# sch_Connet_IMU.net
KiCad netlist of a schematic drawn in Altium Designer
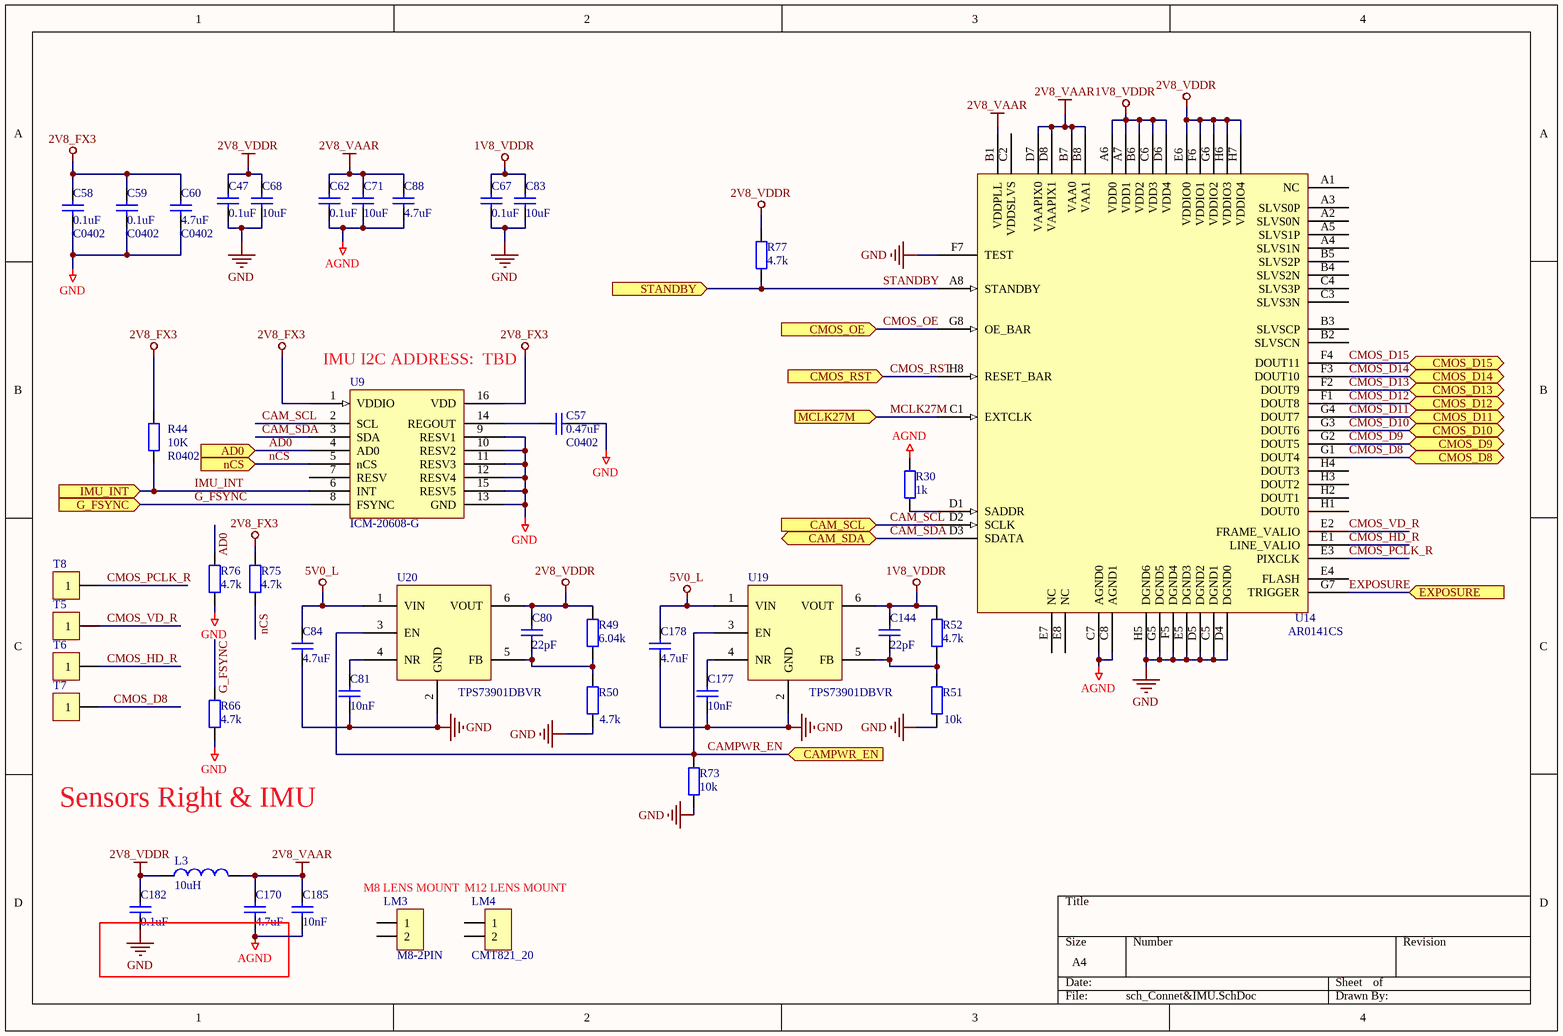
[diagram p0: sch_Connet&IMU.SchDoc]

(export (version "E")
  (design (tool "Eeschema 10.0.6"))
  (components
    (comp (ref "C47")
      (value "0.1uF")
      (footprint "0402C")
      (description "Capacitor")
      (fields (field (name "PUBLISHER") "Altium Limited"))
      (libsource (lib "Miscellaneous Devices") (part "Cap"))
    )
    (comp (ref "C57")
      (value "0.47uF")
      (footprint "0402C")
      (description "Capacitor")
      (fields (field (name "ALTIUM_VALUE") "C0402") (field (name "PUBLISHER") "Altium Limited"))
      (libsource (lib "Miscellaneous Devices") (part "Cap"))
    )
    (comp (ref "C58")
      (value "0.1uF")
      (footprint "0402C")
      (description "Capacitor")
      (fields (field (name "ALTIUM_VALUE") "C0402") (field (name "PUBLISHER") "Altium Limited"))
      (libsource (lib "Miscellaneous Devices") (part "Cap"))
    )
    (comp (ref "C59")
      (value "0.1uF")
      (footprint "0402C")
      (description "Capacitor")
      (fields (field (name "ALTIUM_VALUE") "C0402") (field (name "PUBLISHER") "Altium Limited"))
      (libsource (lib "Miscellaneous Devices") (part "Cap"))
    )
    (comp (ref "C60")
      (value "4.7uF")
      (footprint "0402C")
      (description "Capacitor")
      (fields (field (name "ALTIUM_VALUE") "C0402") (field (name "PUBLISHER") "Altium Limited"))
      (libsource (lib "Miscellaneous Devices") (part "Cap"))
    )
    (comp (ref "C62")
      (value "0.1uF")
      (footprint "0402C")
      (description "Capacitor")
      (fields (field (name "PUBLISHER") "Altium Limited"))
      (libsource (lib "Miscellaneous Devices") (part "Cap"))
    )
    (comp (ref "C67")
      (value "0.1uF")
      (footprint "0402C")
      (description "Capacitor")
      (fields (field (name "PUBLISHER") "Altium Limited"))
      (libsource (lib "Miscellaneous Devices") (part "Cap"))
    )
    (comp (ref "C68")
      (value "10uF")
      (footprint "0805C")
      (description "Capacitor")
      (fields (field (name "PUBLISHER") "Altium Limited"))
      (libsource (lib "Miscellaneous Devices") (part "Cap"))
    )
    (comp (ref "C71")
      (value "10uF")
      (footprint "0805C")
      (description "Capacitor")
      (fields (field (name "PUBLISHER") "Altium Limited"))
      (libsource (lib "Miscellaneous Devices") (part "Cap"))
    )
    (comp (ref "C80")
      (value "22pF")
      (footprint "0805C")
      (description "Capacitor")
      (fields (field (name "PUBLISHER") "Altium Limited"))
      (libsource (lib "Miscellaneous Devices") (part "Cap"))
    )
    (comp (ref "C81")
      (value "10nF")
      (footprint "0402C_L")
      (description "Capacitor")
      (fields (field (name "PUBLISHER") "Altium Limited"))
      (libsource (lib "Miscellaneous Devices") (part "Cap"))
    )
    (comp (ref "C83")
      (value "10uF")
      (footprint "0805C")
      (description "Capacitor")
      (fields (field (name "PUBLISHER") "Altium Limited"))
      (libsource (lib "Miscellaneous Devices") (part "Cap"))
    )
    (comp (ref "C84")
      (value "4.7uF")
      (footprint "0402C_L")
      (description "Capacitor")
      (fields (field (name "PUBLISHER") "Altium Limited"))
      (libsource (lib "Miscellaneous Devices") (part "Cap"))
    )
    (comp (ref "C88")
      (value "4.7uF")
      (footprint "0805C")
      (description "Capacitor")
      (fields (field (name "PUBLISHER") "Altium Limited"))
      (libsource (lib "Miscellaneous Devices") (part "Cap"))
    )
    (comp (ref "C144")
      (value "22pF")
      (footprint "0402C")
      (description "Capacitor")
      (fields (field (name "PUBLISHER") "Altium Limited"))
      (libsource (lib "Miscellaneous Devices") (part "Cap"))
    )
    (comp (ref "C170")
      (value "4.7uF")
      (footprint "0402C")
      (description "Capacitor")
      (fields (field (name "PUBLISHER") "Altium Limited"))
      (libsource (lib "Miscellaneous Devices") (part "Cap"))
    )
    (comp (ref "C177")
      (value "10nF")
      (footprint "0402C_L")
      (description "Capacitor")
      (fields (field (name "PUBLISHER") "Altium Limited"))
      (libsource (lib "Miscellaneous Devices") (part "Cap"))
    )
    (comp (ref "C178")
      (value "4.7uF")
      (footprint "0402C_L")
      (description "Capacitor")
      (fields (field (name "PUBLISHER") "Altium Limited"))
      (libsource (lib "Miscellaneous Devices") (part "Cap"))
    )
    (comp (ref "C182")
      (value "0.1uF")
      (footprint "0402C_L")
      (description "Capacitor")
      (fields (field (name "PUBLISHER") "Altium Limited"))
      (libsource (lib "Miscellaneous Devices") (part "Cap"))
    )
    (comp (ref "C185")
      (value "10nF")
      (footprint "0402C_L")
      (description "Capacitor")
      (fields (field (name "PUBLISHER") "Altium Limited"))
      (libsource (lib "Miscellaneous Devices") (part "Cap"))
    )
    (comp (ref "L3")
      (value "10uH")
      (footprint "0805R")
      (description "Inductor")
      (libsource (lib "SWUST_ROBOT") (part "Inductor"))
    )
    (comp (ref "LM3")
      (value "M8-2PIN")
      (footprint "PAD_M3_D350_450")
      (description "Connector")
      (libsource (lib "SuperSchLib") (part "CON2"))
    )
    (comp (ref "LM4")
      (value "CMT821_20")
      (footprint "PAD_M3_D350_450")
      (description "Connector")
      (libsource (lib "SuperSchLib") (part "CON2"))
    )
    (comp (ref "R30")
      (value "1k")
      (footprint "0402R")
      (description "Resistor")
      (fields (field (name "PUBLISHER") "Altium Limited"))
      (libsource (lib "") (part "Res2_1"))
    )
    (comp (ref "R44")
      (value "10K")
      (footprint "0402R")
      (description "Resistor")
      (fields (field (name "ALTIUM_VALUE") "R0402") (field (name "PUBLISHER") "Altium Limited"))
      (libsource (lib "Miscellaneous Devices") (part "Res2"))
    )
    (comp (ref "R49")
      (value "6.04k")
      (footprint "0402R")
      (description "Resistor")
      (fields (field (name "Comment") "6.04K") (field (name "PUBLISHER") "Altium Limited"))
      (libsource (lib "") (part "Resistor_1"))
    )
    (comp (ref "R50")
      (value "4.7k")
      (footprint "0402R")
      (description "Resistor")
      (fields (field (name "Comment") "4.7K") (field (name "PUBLISHER") "Altium Limited"))
      (libsource (lib "SZG") (part "Resistor"))
    )
    (comp (ref "R51")
      (value "10k")
      (footprint "0402R")
      (description "Resistor")
      (fields (field (name "Comment") "10K") (field (name "PUBLISHER") "Altium Limited"))
      (libsource (lib "SZG") (part "Resistor"))
    )
    (comp (ref "R52")
      (value "4.7k")
      (footprint "0402R")
      (description "Resistor")
      (fields (field (name "Comment") "4.7K") (field (name "PUBLISHER") "Altium Limited"))
      (libsource (lib "") (part "Resistor_1"))
    )
    (comp (ref "R66")
      (value "4.7k")
      (footprint "0402R")
      (description "Resistor")
      (fields (field (name "Comment") "4.7K") (field (name "PUBLISHER") "Altium Limited"))
      (libsource (lib "") (part "Resistor_1"))
    )
    (comp (ref "R73")
      (value "10k")
      (footprint "0402R_L")
      (description "Resistor")
      (fields (field (name "Comment") "10K") (field (name "PUBLISHER") "Altium Limited"))
      (libsource (lib "") (part "Resistor_2"))
    )
    (comp (ref "R75")
      (value "4.7k")
      (footprint "0402R")
      (description "Resistor")
      (fields (field (name "Comment") "4.7K") (field (name "PUBLISHER") "Altium Limited"))
      (libsource (lib "") (part "Resistor_1"))
    )
    (comp (ref "R76")
      (value "4.7k")
      (footprint "0402R")
      (description "Resistor")
      (fields (field (name "Comment") "4.7K") (field (name "PUBLISHER") "Altium Limited"))
      (libsource (lib "") (part "Resistor_1"))
    )
    (comp (ref "R77")
      (value "4.7k")
      (footprint "0402R")
      (description "Resistor")
      (fields (field (name "Comment") "4.7K") (field (name "PUBLISHER") "Altium Limited"))
      (libsource (lib "") (part "Resistor_1"))
    )
    (comp (ref "T5")
      (value "CON1")
      (footprint "PAD_TP_D1.2")
      (description "Connector")
      (libsource (lib "SuperSchLib") (part "CON1"))
    )
    (comp (ref "T6")
      (value "CON1")
      (footprint "PAD_TP_D1.2")
      (description "Connector")
      (libsource (lib "SuperSchLib") (part "CON1"))
    )
    (comp (ref "T7")
      (value "CON1")
      (footprint "PAD_TP_D1.2")
      (description "Connector")
      (libsource (lib "SuperSchLib") (part "CON1"))
    )
    (comp (ref "T8")
      (value "CON1")
      (footprint "PAD_TP_D1.2")
      (description "Connector")
      (libsource (lib "SuperSchLib") (part "CON1"))
    )
    (comp (ref "U9")
      (value "ICM-20608-G")
      (footprint "LGA16_P50L30W30H08")
      (libsource (lib "SZG") (part "ICM-20608-G"))
    )
    (comp (ref "U14") (value "AR0141CS") (libsource (lib "TXW") (part "AR0141CS")))
    (comp (ref "U19") (value "TPS73901DBVR") (libsource (lib "SZG") (part "TPS73901DBVR")))
    (comp (ref "U20") (value "TPS73901DBVR") (libsource (lib "SZG") (part "TPS73901DBVR")))
  )
  (nets
    (net (code "1") (name "/AD0") (class "Default")
      (node (ref "R76") (pin "2") (pinfunction "2_2") (pintype "passive"))
      (node (ref "U9") (pin "4") (pinfunction "AD0_4") (pintype "passive"))
    )
    (net (code "2") (name "/CAMPWR_EN") (class "Default")
      (node (ref "R73") (pin "1") (pinfunction "1_1") (pintype "passive"))
      (node (ref "U19") (pin "3") (pinfunction "EN_3") (pintype "passive"))
      (node (ref "U20") (pin "3") (pinfunction "EN_3") (pintype "passive"))
    )
    (net (code "3") (name "/CAM_SCL") (class "Default")
      (node (ref "U14") (pin "D2") (pinfunction "SCLK_D2") (pintype "input"))
      (node (ref "U9") (pin "2") (pinfunction "SCL_2") (pintype "passive"))
    )
    (net (code "4") (name "/CAM_SDA") (class "Default")
      (node (ref "U14") (pin "D3") (pinfunction "SDATA_D3") (pintype "passive"))
      (node (ref "U9") (pin "3") (pinfunction "SDA_3") (pintype "passive"))
    )
    (net (code "5") (name "/CMOS_D8") (class "Default")
      (node (ref "T7") (pin "1") (pinfunction "1_1") (pintype "passive"))
      (node (ref "U14") (pin "G1") (pinfunction "DOUT4_G1") (pintype "passive"))
    )
    (net (code "6") (name "/CMOS_D9") (class "Default")
      (node (ref "U14") (pin "G2") (pinfunction "DOUT5_G2") (pintype "passive"))
    )
    (net (code "7") (name "/CMOS_D10") (class "Default")
      (node (ref "U14") (pin "G3") (pinfunction "DOUT6_G3") (pintype "passive"))
    )
    (net (code "8") (name "/CMOS_D11") (class "Default")
      (node (ref "U14") (pin "G4") (pinfunction "DOUT7_G4") (pintype "passive"))
    )
    (net (code "9") (name "/CMOS_D12") (class "Default")
      (node (ref "U14") (pin "F1") (pinfunction "DOUT8_F1") (pintype "passive"))
    )
    (net (code "10") (name "/CMOS_D13") (class "Default")
      (node (ref "U14") (pin "F2") (pinfunction "DOUT9_F2") (pintype "passive"))
    )
    (net (code "11") (name "/CMOS_D14") (class "Default")
      (node (ref "U14") (pin "F3") (pinfunction "DOUT10_F3") (pintype "passive"))
    )
    (net (code "12") (name "/CMOS_D15") (class "Default")
      (node (ref "U14") (pin "F4") (pinfunction "DOUT11_F4") (pintype "passive"))
    )
    (net (code "13") (name "/CMOS_HD_R") (class "Default")
      (node (ref "T6") (pin "1") (pinfunction "1_1") (pintype "passive"))
      (node (ref "U14") (pin "E1") (pinfunction "LINE_VALIO_E1") (pintype "passive"))
    )
    (net (code "14") (name "/CMOS_OE") (class "Default")
      (node (ref "U14") (pin "G8") (pinfunction "OE_BAR_G8") (pintype "input"))
    )
    (net (code "15") (name "/CMOS_PCLK_R") (class "Default")
      (node (ref "T8") (pin "1") (pinfunction "1_1") (pintype "passive"))
      (node (ref "U14") (pin "E3") (pinfunction "PIXCLK_E3") (pintype "passive"))
    )
    (net (code "16") (name "/CMOS_RST") (class "Default")
      (node (ref "U14") (pin "H8") (pinfunction "RESET_BAR_H8") (pintype "input"))
    )
    (net (code "17") (name "/CMOS_VD_R") (class "Default")
      (node (ref "T5") (pin "1") (pinfunction "1_1") (pintype "passive"))
      (node (ref "U14") (pin "E2") (pinfunction "FRAME_VALIO_E2") (pintype "passive"))
    )
    (net (code "18") (name "/EXPOSURE") (class "Default")
      (node (ref "U14") (pin "G7") (pinfunction "TRIGGER_G7") (pintype "passive"))
    )
    (net (code "19") (name "/G_FSYNC") (class "Default")
      (node (ref "R66") (pin "2") (pinfunction "2_2") (pintype "passive"))
      (node (ref "U9") (pin "8") (pinfunction "FSYNC_8") (pintype "passive"))
    )
    (net (code "20") (name "/IMU_INT") (class "Default")
      (node (ref "R44") (pin "1") (pinfunction "1_1") (pintype "passive"))
      (node (ref "U9") (pin "6") (pinfunction "INT_6") (pintype "passive"))
    )
    (net (code "21") (name "/MCLK27M") (class "Default")
      (node (ref "U14") (pin "C1") (pinfunction "EXTCLK_C1") (pintype "input"))
    )
    (net (code "22") (name "/STANDBY") (class "Default")
      (node (ref "R77") (pin "1") (pinfunction "1_1") (pintype "passive"))
      (node (ref "U14") (pin "A8") (pinfunction "STANDBY_A8") (pintype "input"))
    )
    (net (code "23") (name "/nCS") (class "Default")
      (node (ref "R75") (pin "1") (pinfunction "1_1") (pintype "passive"))
      (node (ref "U9") (pin "5") (pinfunction "nCS_5") (pintype "passive"))
    )
    (net (code "24") (name "1V8_VDDR") (class "Default")
      (node (ref "C144") (pin "2") (pinfunction "2_2") (pintype "passive"))
      (node (ref "C67") (pin "2") (pinfunction "2_2") (pintype "passive"))
      (node (ref "C83") (pin "2") (pinfunction "2_2") (pintype "passive"))
      (node (ref "R52") (pin "2") (pinfunction "2_2") (pintype "passive"))
      (node (ref "U14") (pin "A6") (pinfunction "VDD0_A6") (pintype "power_in"))
      (node (ref "U14") (pin "A7") (pinfunction "VDD1_A7") (pintype "power_in"))
      (node (ref "U14") (pin "B6") (pinfunction "VDD2_B6") (pintype "power_in"))
      (node (ref "U14") (pin "C6") (pinfunction "VDD3_C6") (pintype "power_in"))
      (node (ref "U14") (pin "D6") (pinfunction "VDD4_D6") (pintype "power_in"))
      (node (ref "U19") (pin "6") (pinfunction "VOUT_6") (pintype "passive"))
    )
    (net (code "25") (name "2V8_FX3") (class "Default")
      (node (ref "C58") (pin "2") (pinfunction "2_2") (pintype "passive"))
      (node (ref "C59") (pin "2") (pinfunction "2_2") (pintype "passive"))
      (node (ref "C60") (pin "2") (pinfunction "2_2") (pintype "passive"))
      (node (ref "R44") (pin "2") (pinfunction "2_2") (pintype "passive"))
      (node (ref "R75") (pin "2") (pinfunction "2_2") (pintype "passive"))
      (node (ref "U9") (pin "1") (pinfunction "VDDIO_1") (pintype "input"))
      (node (ref "U9") (pin "16") (pinfunction "VDD_16") (pintype "passive"))
    )
    (net (code "26") (name "2V8_VAAR") (class "Default")
      (node (ref "C170") (pin "2") (pinfunction "2_2") (pintype "passive"))
      (node (ref "C185") (pin "2") (pinfunction "2_2") (pintype "passive"))
      (node (ref "C62") (pin "2") (pinfunction "2_2") (pintype "passive"))
      (node (ref "C71") (pin "2") (pinfunction "2_2") (pintype "passive"))
      (node (ref "C88") (pin "2") (pinfunction "2_2") (pintype "passive"))
      (node (ref "L3") (pin "2") (pinfunction "2_2") (pintype "passive"))
      (node (ref "U14") (pin "B1") (pinfunction "VDDPLL_B1") (pintype "power_in"))
      (node (ref "U14") (pin "B7") (pinfunction "VAA0_B7") (pintype "power_in"))
      (node (ref "U14") (pin "B8") (pinfunction "VAA1_B8") (pintype "power_in"))
      (node (ref "U14") (pin "D7") (pinfunction "VAAPIX0_D7") (pintype "power_in"))
      (node (ref "U14") (pin "D8") (pinfunction "VAAPIX1_D8") (pintype "power_in"))
    )
    (net (code "27") (name "2V8_VDDR") (class "Default")
      (node (ref "C182") (pin "2") (pinfunction "2_2") (pintype "passive"))
      (node (ref "C47") (pin "2") (pinfunction "2_2") (pintype "passive"))
      (node (ref "C68") (pin "2") (pinfunction "2_2") (pintype "passive"))
      (node (ref "C80") (pin "2") (pinfunction "2_2") (pintype "passive"))
      (node (ref "L3") (pin "1") (pinfunction "1_1") (pintype "passive"))
      (node (ref "R49") (pin "2") (pinfunction "2_2") (pintype "passive"))
      (node (ref "R77") (pin "2") (pinfunction "2_2") (pintype "passive"))
      (node (ref "U14") (pin "E6") (pinfunction "VDDIO0_E6") (pintype "power_in"))
      (node (ref "U14") (pin "F6") (pinfunction "VDDIO1_F6") (pintype "power_in"))
      (node (ref "U14") (pin "G6") (pinfunction "VDDIO2_G6") (pintype "power_in"))
      (node (ref "U14") (pin "H6") (pinfunction "VDDIO3_H6") (pintype "power_in"))
      (node (ref "U14") (pin "H7") (pinfunction "VDDIO4_H7") (pintype "power_in"))
      (node (ref "U20") (pin "6") (pinfunction "VOUT_6") (pintype "passive"))
    )
    (net (code "28") (name "5V0_L") (class "Default")
      (node (ref "C178") (pin "2") (pinfunction "2_2") (pintype "passive"))
      (node (ref "C84") (pin "2") (pinfunction "2_2") (pintype "passive"))
      (node (ref "U19") (pin "1") (pinfunction "VIN_1") (pintype "passive"))
      (node (ref "U20") (pin "1") (pinfunction "VIN_1") (pintype "passive"))
    )
    (net (code "29") (name "AGND") (class "Default")
      (node (ref "C170") (pin "1") (pinfunction "1_1") (pintype "passive"))
      (node (ref "C185") (pin "1") (pinfunction "1_1") (pintype "passive"))
      (node (ref "C62") (pin "1") (pinfunction "1_1") (pintype "passive"))
      (node (ref "C71") (pin "1") (pinfunction "1_1") (pintype "passive"))
      (node (ref "C88") (pin "1") (pinfunction "1_1") (pintype "passive"))
      (node (ref "R30") (pin "1") (pinfunction "1_1") (pintype "passive"))
      (node (ref "U14") (pin "C7") (pinfunction "AGND0_C7") (pintype "power_in"))
      (node (ref "U14") (pin "C8") (pinfunction "AGND1_C8") (pintype "power_in"))
    )
    (net (code "30") (name "GND") (class "Default")
      (node (ref "C177") (pin "1") (pinfunction "1_1") (pintype "passive"))
      (node (ref "C178") (pin "1") (pinfunction "1_1") (pintype "passive"))
      (node (ref "C182") (pin "1") (pinfunction "1_1") (pintype "passive"))
      (node (ref "C47") (pin "1") (pinfunction "1_1") (pintype "passive"))
      (node (ref "C57") (pin "1") (pinfunction "1_1") (pintype "passive"))
      (node (ref "C58") (pin "1") (pinfunction "1_1") (pintype "passive"))
      (node (ref "C59") (pin "1") (pinfunction "1_1") (pintype "passive"))
      (node (ref "C60") (pin "1") (pinfunction "1_1") (pintype "passive"))
      (node (ref "C67") (pin "1") (pinfunction "1_1") (pintype "passive"))
      (node (ref "C68") (pin "1") (pinfunction "1_1") (pintype "passive"))
      (node (ref "C81") (pin "1") (pinfunction "1_1") (pintype "passive"))
      (node (ref "C83") (pin "1") (pinfunction "1_1") (pintype "passive"))
      (node (ref "C84") (pin "1") (pinfunction "1_1") (pintype "passive"))
      (node (ref "R50") (pin "2") (pinfunction "2_2") (pintype "passive"))
      (node (ref "R51") (pin "2") (pinfunction "2_2") (pintype "passive"))
      (node (ref "R66") (pin "1") (pinfunction "1_1") (pintype "passive"))
      (node (ref "R73") (pin "2") (pinfunction "2_2") (pintype "passive"))
      (node (ref "R76") (pin "1") (pinfunction "1_1") (pintype "passive"))
      (node (ref "U14") (pin "C5") (pinfunction "DGND1_C5") (pintype "power_in"))
      (node (ref "U14") (pin "D4") (pinfunction "DGND0_D4") (pintype "power_in"))
      (node (ref "U14") (pin "D5") (pinfunction "DGND2_D5") (pintype "power_in"))
      (node (ref "U14") (pin "E5") (pinfunction "DGND3_E5") (pintype "power_in"))
      (node (ref "U14") (pin "F5") (pinfunction "DGND4_F5") (pintype "power_in"))
      (node (ref "U14") (pin "F7") (pinfunction "TEST_F7") (pintype "passive"))
      (node (ref "U14") (pin "G5") (pinfunction "DGND5_G5") (pintype "power_in"))
      (node (ref "U14") (pin "H5") (pinfunction "DGND6_H5") (pintype "power_in"))
      (node (ref "U19") (pin "2") (pinfunction "GND_2") (pintype "passive"))
      (node (ref "U20") (pin "2") (pinfunction "GND_2") (pintype "passive"))
      (node (ref "U9") (pin "10") (pinfunction "RESV2_10") (pintype "passive"))
      (node (ref "U9") (pin "11") (pinfunction "RESV3_11") (pintype "passive"))
      (node (ref "U9") (pin "12") (pinfunction "RESV4_12") (pintype "passive"))
      (node (ref "U9") (pin "13") (pinfunction "GND_13") (pintype "passive"))
      (node (ref "U9") (pin "15") (pinfunction "RESV5_15") (pintype "passive"))
      (node (ref "U9") (pin "9") (pinfunction "RESV1_9") (pintype "passive"))
    )
    (net (code "31") (name "Net-(U9-REGOUT)") (class "Default")
      (node (ref "C57") (pin "2") (pinfunction "2_2") (pintype "passive"))
      (node (ref "U9") (pin "14") (pinfunction "REGOUT_14") (pintype "passive"))
    )
    (net (code "32") (name "Net-(U14-SADDR)") (class "Default")
      (node (ref "R30") (pin "2") (pinfunction "2_2") (pintype "passive"))
      (node (ref "U14") (pin "D1") (pinfunction "SADDR_D1") (pintype "input"))
    )
    (net (code "33") (name "Net-(U19-FB)") (class "Default")
      (node (ref "C144") (pin "1") (pinfunction "1_1") (pintype "passive"))
      (node (ref "R51") (pin "1") (pinfunction "1_1") (pintype "passive"))
      (node (ref "R52") (pin "1") (pinfunction "1_1") (pintype "passive"))
      (node (ref "U19") (pin "5") (pinfunction "FB_5") (pintype "passive"))
    )
    (net (code "34") (name "Net-(U19-NR)") (class "Default")
      (node (ref "C177") (pin "2") (pinfunction "2_2") (pintype "passive"))
      (node (ref "U19") (pin "4") (pinfunction "NR_4") (pintype "passive"))
    )
    (net (code "35") (name "Net-(U20-FB)") (class "Default")
      (node (ref "C80") (pin "1") (pinfunction "1_1") (pintype "passive"))
      (node (ref "R49") (pin "1") (pinfunction "1_1") (pintype "passive"))
      (node (ref "R50") (pin "1") (pinfunction "1_1") (pintype "passive"))
      (node (ref "U20") (pin "5") (pinfunction "FB_5") (pintype "passive"))
    )
    (net (code "36") (name "Net-(U20-NR)") (class "Default")
      (node (ref "C81") (pin "2") (pinfunction "2_2") (pintype "passive"))
      (node (ref "U20") (pin "4") (pinfunction "NR_4") (pintype "passive"))
    )
    (net (code "37") (name "unconnected-(LM3-Pad1)") (class "Default")
      (node (ref "LM3") (pin "1") (pinfunction "1_1") (pintype "passive"))
    )
    (net (code "38") (name "unconnected-(LM3-Pad2)") (class "Default")
      (node (ref "LM3") (pin "2") (pinfunction "2_2") (pintype "passive"))
    )
    (net (code "39") (name "unconnected-(LM4-Pad1)") (class "Default")
      (node (ref "LM4") (pin "1") (pinfunction "1_1") (pintype "passive"))
    )
    (net (code "40") (name "unconnected-(LM4-Pad2)") (class "Default")
      (node (ref "LM4") (pin "2") (pinfunction "2_2") (pintype "passive"))
    )
    (net (code "41") (name "unconnected-(U9-RESV-Pad7)") (class "Default")
      (node (ref "U9") (pin "7") (pinfunction "RESV_7") (pintype "passive"))
    )
    (net (code "42") (name "unconnected-(U14-DOUT0-PadH1)") (class "Default")
      (node (ref "U14") (pin "H1") (pinfunction "DOUT0_H1") (pintype "passive"))
    )
    (net (code "43") (name "unconnected-(U14-DOUT1-PadH2)") (class "Default")
      (node (ref "U14") (pin "H2") (pinfunction "DOUT1_H2") (pintype "passive"))
    )
    (net (code "44") (name "unconnected-(U14-DOUT2-PadH3)") (class "Default")
      (node (ref "U14") (pin "H3") (pinfunction "DOUT2_H3") (pintype "passive"))
    )
    (net (code "45") (name "unconnected-(U14-DOUT3-PadH4)") (class "Default")
      (node (ref "U14") (pin "H4") (pinfunction "DOUT3_H4") (pintype "passive"))
    )
    (net (code "46") (name "unconnected-(U14-FLASH-PadE4)") (class "Default")
      (node (ref "U14") (pin "E4") (pinfunction "FLASH_E4") (pintype "passive"))
    )
    (net (code "47") (name "unconnected-(U14-NC-PadA1)") (class "Default")
      (node (ref "U14") (pin "A1") (pinfunction "NC_A1") (pintype "passive"))
    )
    (net (code "48") (name "unconnected-(U14-NC-PadE7)") (class "Default")
      (node (ref "U14") (pin "E7") (pinfunction "NC_E7") (pintype "passive"))
    )
    (net (code "49") (name "unconnected-(U14-NC-PadE8)") (class "Default")
      (node (ref "U14") (pin "E8") (pinfunction "NC_E8") (pintype "passive"))
    )
    (net (code "50") (name "unconnected-(U14-SLVS0N-PadA2)") (class "Default")
      (node (ref "U14") (pin "A2") (pinfunction "SLVS0N_A2") (pintype "passive"))
    )
    (net (code "51") (name "unconnected-(U14-SLVS0P-PadA3)") (class "Default")
      (node (ref "U14") (pin "A3") (pinfunction "SLVS0P_A3") (pintype "passive"))
    )
    (net (code "52") (name "unconnected-(U14-SLVS1N-PadA4)") (class "Default")
      (node (ref "U14") (pin "A4") (pinfunction "SLVS1N_A4") (pintype "passive"))
    )
    (net (code "53") (name "unconnected-(U14-SLVS1P-PadA5)") (class "Default")
      (node (ref "U14") (pin "A5") (pinfunction "SLVS1P_A5") (pintype "passive"))
    )
    (net (code "54") (name "unconnected-(U14-SLVS2N-PadB4)") (class "Default")
      (node (ref "U14") (pin "B4") (pinfunction "SLVS2N_B4") (pintype "passive"))
    )
    (net (code "55") (name "unconnected-(U14-SLVS2P-PadB5)") (class "Default")
      (node (ref "U14") (pin "B5") (pinfunction "SLVS2P_B5") (pintype "passive"))
    )
    (net (code "56") (name "unconnected-(U14-SLVS3N-PadC3)") (class "Default")
      (node (ref "U14") (pin "C3") (pinfunction "SLVS3N_C3") (pintype "passive"))
    )
    (net (code "57") (name "unconnected-(U14-SLVS3P-PadC4)") (class "Default")
      (node (ref "U14") (pin "C4") (pinfunction "SLVS3P_C4") (pintype "passive"))
    )
    (net (code "58") (name "unconnected-(U14-SLVSCN-PadB2)") (class "Default")
      (node (ref "U14") (pin "B2") (pinfunction "SLVSCN_B2") (pintype "passive"))
    )
    (net (code "59") (name "unconnected-(U14-SLVSCP-PadB3)") (class "Default")
      (node (ref "U14") (pin "B3") (pinfunction "SLVSCP_B3") (pintype "passive"))
    )
    (net (code "60") (name "unconnected-(U14-VDDSLVS-PadC2)") (class "Default")
      (node (ref "U14") (pin "C2") (pinfunction "VDDSLVS_C2") (pintype "power_in"))
    )
  )
)
